# GPIOs.net
KiCad netlist of a schematic drawn in Altium Designer
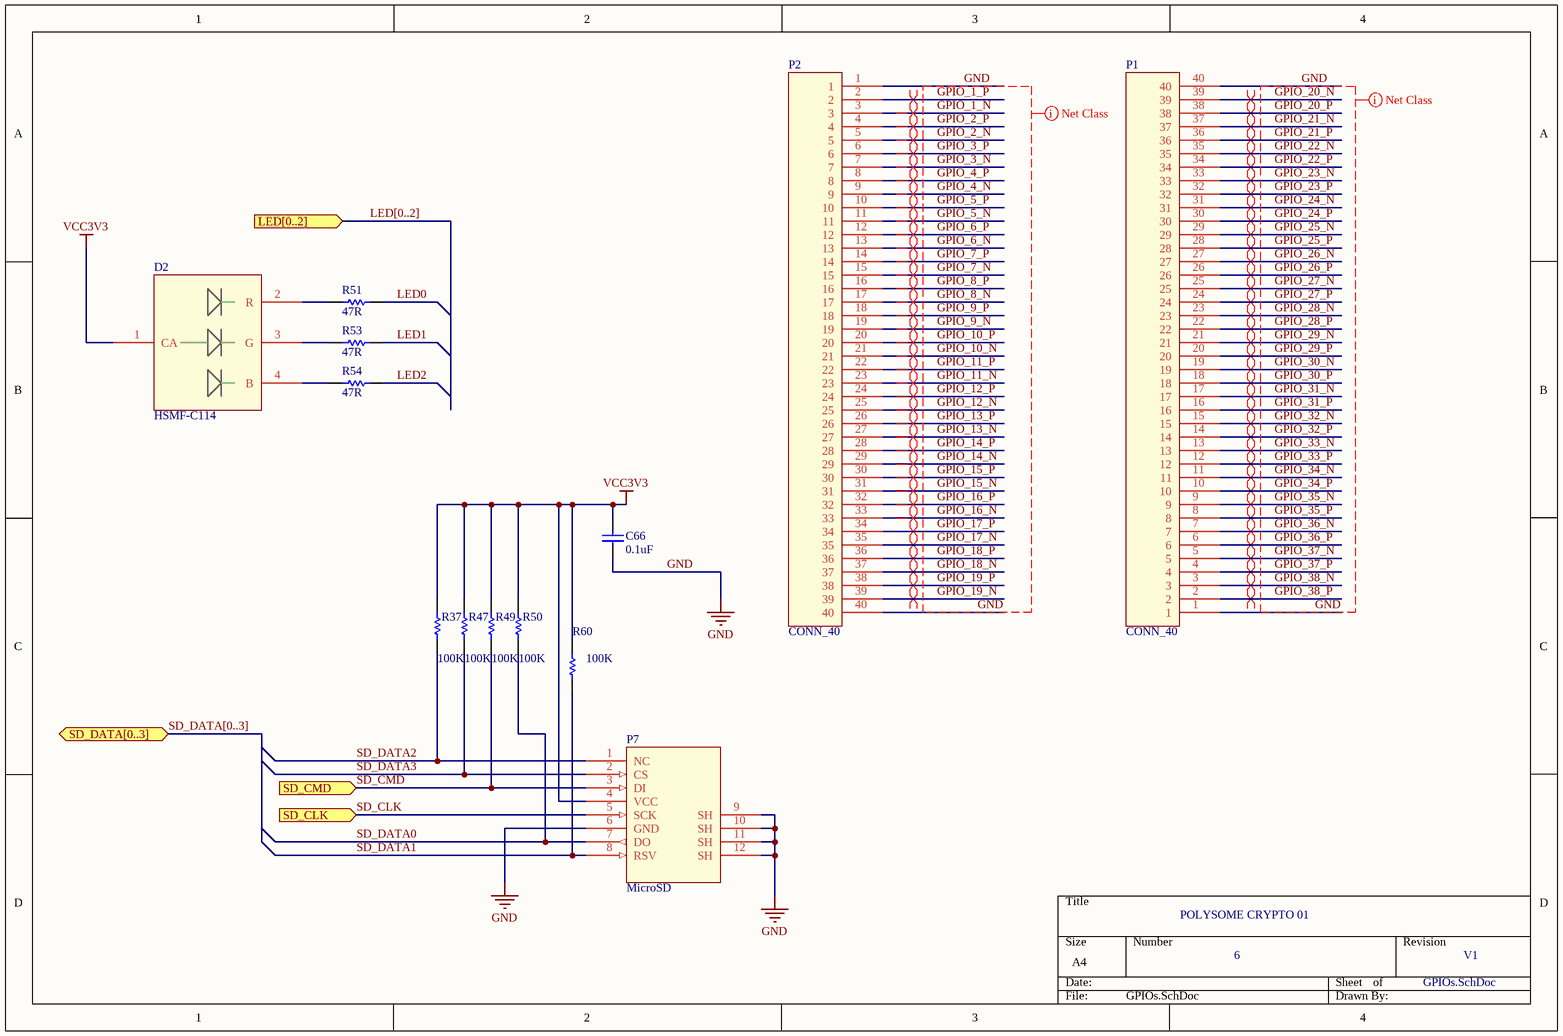
[diagram p0: GPIOs.SchDoc]

(export (version "E")
  (design (tool "Eeschema 10.0.6"))
  (components
    (comp (ref "C66")
      (value "0.1uF")
      (footprint "0402")
      (description "Capacitor (Semiconductor SIM Model)")
      (fields (field (name "Comment") "Cap Semi") (field (name "PUBLISHER") "Altium Limited"))
      (libsource (lib "Miscellaneous Devices") (part "Cap Semi"))
    )
    (comp (ref "D2")
      (value "HSMF-C114")
      (footprint "DFN110P150X35-4N")
      (description "LED CHIP RGB 1.6X1.5X0.35MM SMD")
      (fields (field (name "MANUFACTURER") "Avago Technologies US Inc."))
      (libsource (lib "PolySomeCrypto01") (part "HSMF-C114"))
    )
    (comp (ref "P1")
      (value "CONN_40")
      (footprint "FH12-40S-0.5SH")
      (libsource (lib "PolySomeCrypto01") (part "CONN_40"))
    )
    (comp (ref "P2") (value "CONN_40") (footprint "FH12-40S-0.5SH") (libsource (lib "") (part "CONN_40_1")))
    (comp (ref "P7")
      (value "MicroSD")
      (footprint "MicroSD")
      (libsource (lib "PolySomeCrypto01") (part "MicroSD"))
    )
    (comp (ref "R37")
      (value "100K")
      (description "Semiconductor Resistor")
      (fields (field (name "Comment") "Res Semi") (field (name "PUBLISHER") "Altium Limited"))
      (libsource (lib "Miscellaneous Devices") (part "Res Semi"))
    )
    (comp (ref "R47")
      (value "100K")
      (description "Semiconductor Resistor")
      (fields (field (name "Comment") "Res Semi") (field (name "PUBLISHER") "Altium Limited"))
      (libsource (lib "Miscellaneous Devices") (part "Res Semi"))
    )
    (comp (ref "R49")
      (value "100K")
      (description "Semiconductor Resistor")
      (fields (field (name "Comment") "Res Semi") (field (name "PUBLISHER") "Altium Limited"))
      (libsource (lib "Miscellaneous Devices") (part "Res Semi"))
    )
    (comp (ref "R50")
      (value "100K")
      (description "Semiconductor Resistor")
      (fields (field (name "Comment") "Res Semi") (field (name "PUBLISHER") "Altium Limited"))
      (libsource (lib "Miscellaneous Devices") (part "Res Semi"))
    )
    (comp (ref "R51")
      (value "47R")
      (description "Semiconductor Resistor")
      (fields (field (name "Comment") "Res Semi") (field (name "PUBLISHER") "Altium Limited"))
      (libsource (lib "Miscellaneous Devices") (part "Res Semi"))
    )
    (comp (ref "R53")
      (value "47R")
      (description "Semiconductor Resistor")
      (fields (field (name "Comment") "Res Semi") (field (name "PUBLISHER") "Altium Limited"))
      (libsource (lib "Miscellaneous Devices") (part "Res Semi"))
    )
    (comp (ref "R54")
      (value "47R")
      (description "Semiconductor Resistor")
      (fields (field (name "Comment") "Res Semi") (field (name "PUBLISHER") "Altium Limited"))
      (libsource (lib "Miscellaneous Devices") (part "Res Semi"))
    )
    (comp (ref "R60")
      (value "100K")
      (footprint "0402")
      (description "Semiconductor Resistor")
      (fields (field (name "Comment") "Res Semi") (field (name "PUBLISHER") "Altium Limited"))
      (libsource (lib "Miscellaneous Devices") (part "Res Semi"))
    )
  )
  (nets
    (net (code "1") (name "/GPIO_1_N") (class "Default")
      (node (ref "P2") (pin "3") (pinfunction "3_3") (pintype "passive"))
    )
    (net (code "2") (name "/GPIO_1_P") (class "Default")
      (node (ref "P2") (pin "2") (pinfunction "2_2") (pintype "passive"))
    )
    (net (code "3") (name "/GPIO_2_N") (class "Default")
      (node (ref "P2") (pin "5") (pinfunction "5_5") (pintype "passive"))
    )
    (net (code "4") (name "/GPIO_2_P") (class "Default")
      (node (ref "P2") (pin "4") (pinfunction "4_4") (pintype "passive"))
    )
    (net (code "5") (name "/GPIO_3_N") (class "Default")
      (node (ref "P2") (pin "7") (pinfunction "7_7") (pintype "passive"))
    )
    (net (code "6") (name "/GPIO_3_P") (class "Default")
      (node (ref "P2") (pin "6") (pinfunction "6_6") (pintype "passive"))
    )
    (net (code "7") (name "/GPIO_4_N") (class "Default")
      (node (ref "P2") (pin "9") (pinfunction "9_9") (pintype "passive"))
    )
    (net (code "8") (name "/GPIO_4_P") (class "Default")
      (node (ref "P2") (pin "8") (pinfunction "8_8") (pintype "passive"))
    )
    (net (code "9") (name "/GPIO_5_N") (class "Default")
      (node (ref "P2") (pin "11") (pinfunction "11_11") (pintype "passive"))
    )
    (net (code "10") (name "/GPIO_5_P") (class "Default")
      (node (ref "P2") (pin "10") (pinfunction "10_10") (pintype "passive"))
    )
    (net (code "11") (name "/GPIO_6_N") (class "Default")
      (node (ref "P2") (pin "13") (pinfunction "13_13") (pintype "passive"))
    )
    (net (code "12") (name "/GPIO_6_P") (class "Default")
      (node (ref "P2") (pin "12") (pinfunction "12_12") (pintype "passive"))
    )
    (net (code "13") (name "/GPIO_7_N") (class "Default")
      (node (ref "P2") (pin "15") (pinfunction "15_15") (pintype "passive"))
    )
    (net (code "14") (name "/GPIO_7_P") (class "Default")
      (node (ref "P2") (pin "14") (pinfunction "14_14") (pintype "passive"))
    )
    (net (code "15") (name "/GPIO_8_N") (class "Default")
      (node (ref "P2") (pin "17") (pinfunction "17_17") (pintype "passive"))
    )
    (net (code "16") (name "/GPIO_8_P") (class "Default")
      (node (ref "P2") (pin "16") (pinfunction "16_16") (pintype "passive"))
    )
    (net (code "17") (name "/GPIO_9_N") (class "Default")
      (node (ref "P2") (pin "19") (pinfunction "19_19") (pintype "passive"))
    )
    (net (code "18") (name "/GPIO_9_P") (class "Default")
      (node (ref "P2") (pin "18") (pinfunction "18_18") (pintype "passive"))
    )
    (net (code "19") (name "/GPIO_10_N") (class "Default")
      (node (ref "P2") (pin "21") (pinfunction "21_21") (pintype "passive"))
    )
    (net (code "20") (name "/GPIO_10_P") (class "Default")
      (node (ref "P2") (pin "20") (pinfunction "20_20") (pintype "passive"))
    )
    (net (code "21") (name "/GPIO_11_N") (class "Default")
      (node (ref "P2") (pin "23") (pinfunction "23_23") (pintype "passive"))
    )
    (net (code "22") (name "/GPIO_11_P") (class "Default")
      (node (ref "P2") (pin "22") (pinfunction "22_22") (pintype "passive"))
    )
    (net (code "23") (name "/GPIO_12_N") (class "Default")
      (node (ref "P2") (pin "25") (pinfunction "25_25") (pintype "passive"))
    )
    (net (code "24") (name "/GPIO_12_P") (class "Default")
      (node (ref "P2") (pin "24") (pinfunction "24_24") (pintype "passive"))
    )
    (net (code "25") (name "/GPIO_13_N") (class "Default")
      (node (ref "P2") (pin "27") (pinfunction "27_27") (pintype "passive"))
    )
    (net (code "26") (name "/GPIO_13_P") (class "Default")
      (node (ref "P2") (pin "26") (pinfunction "26_26") (pintype "passive"))
    )
    (net (code "27") (name "/GPIO_14_N") (class "Default")
      (node (ref "P2") (pin "29") (pinfunction "29_29") (pintype "passive"))
    )
    (net (code "28") (name "/GPIO_14_P") (class "Default")
      (node (ref "P2") (pin "28") (pinfunction "28_28") (pintype "passive"))
    )
    (net (code "29") (name "/GPIO_15_N") (class "Default")
      (node (ref "P2") (pin "31") (pinfunction "31_31") (pintype "passive"))
    )
    (net (code "30") (name "/GPIO_15_P") (class "Default")
      (node (ref "P2") (pin "30") (pinfunction "30_30") (pintype "passive"))
    )
    (net (code "31") (name "/GPIO_16_N") (class "Default")
      (node (ref "P2") (pin "33") (pinfunction "33_33") (pintype "passive"))
    )
    (net (code "32") (name "/GPIO_16_P") (class "Default")
      (node (ref "P2") (pin "32") (pinfunction "32_32") (pintype "passive"))
    )
    (net (code "33") (name "/GPIO_17_N") (class "Default")
      (node (ref "P2") (pin "35") (pinfunction "35_35") (pintype "passive"))
    )
    (net (code "34") (name "/GPIO_17_P") (class "Default")
      (node (ref "P2") (pin "34") (pinfunction "34_34") (pintype "passive"))
    )
    (net (code "35") (name "/GPIO_18_N") (class "Default")
      (node (ref "P2") (pin "37") (pinfunction "37_37") (pintype "passive"))
    )
    (net (code "36") (name "/GPIO_18_P") (class "Default")
      (node (ref "P2") (pin "36") (pinfunction "36_36") (pintype "passive"))
    )
    (net (code "37") (name "/GPIO_19_N") (class "Default")
      (node (ref "P2") (pin "39") (pinfunction "39_39") (pintype "passive"))
    )
    (net (code "38") (name "/GPIO_19_P") (class "Default")
      (node (ref "P2") (pin "38") (pinfunction "38_38") (pintype "passive"))
    )
    (net (code "39") (name "/GPIO_20_N") (class "Default")
      (node (ref "P1") (pin "39") (pinfunction "39_39") (pintype "passive"))
    )
    (net (code "40") (name "/GPIO_20_P") (class "Default")
      (node (ref "P1") (pin "38") (pinfunction "38_38") (pintype "passive"))
    )
    (net (code "41") (name "/GPIO_21_N") (class "Default")
      (node (ref "P1") (pin "37") (pinfunction "37_37") (pintype "passive"))
    )
    (net (code "42") (name "/GPIO_21_P") (class "Default")
      (node (ref "P1") (pin "36") (pinfunction "36_36") (pintype "passive"))
    )
    (net (code "43") (name "/GPIO_22_N") (class "Default")
      (node (ref "P1") (pin "35") (pinfunction "35_35") (pintype "passive"))
    )
    (net (code "44") (name "/GPIO_22_P") (class "Default")
      (node (ref "P1") (pin "34") (pinfunction "34_34") (pintype "passive"))
    )
    (net (code "45") (name "/GPIO_23_N") (class "Default")
      (node (ref "P1") (pin "33") (pinfunction "33_33") (pintype "passive"))
    )
    (net (code "46") (name "/GPIO_23_P") (class "Default")
      (node (ref "P1") (pin "32") (pinfunction "32_32") (pintype "passive"))
    )
    (net (code "47") (name "/GPIO_24_N") (class "Default")
      (node (ref "P1") (pin "31") (pinfunction "31_31") (pintype "passive"))
    )
    (net (code "48") (name "/GPIO_24_P") (class "Default")
      (node (ref "P1") (pin "30") (pinfunction "30_30") (pintype "passive"))
    )
    (net (code "49") (name "/GPIO_25_N") (class "Default")
      (node (ref "P1") (pin "29") (pinfunction "29_29") (pintype "passive"))
    )
    (net (code "50") (name "/GPIO_25_P") (class "Default")
      (node (ref "P1") (pin "28") (pinfunction "28_28") (pintype "passive"))
    )
    (net (code "51") (name "/GPIO_26_N") (class "Default")
      (node (ref "P1") (pin "27") (pinfunction "27_27") (pintype "passive"))
    )
    (net (code "52") (name "/GPIO_26_P") (class "Default")
      (node (ref "P1") (pin "26") (pinfunction "26_26") (pintype "passive"))
    )
    (net (code "53") (name "/GPIO_27_N") (class "Default")
      (node (ref "P1") (pin "25") (pinfunction "25_25") (pintype "passive"))
    )
    (net (code "54") (name "/GPIO_27_P") (class "Default")
      (node (ref "P1") (pin "24") (pinfunction "24_24") (pintype "passive"))
    )
    (net (code "55") (name "/GPIO_28_N") (class "Default")
      (node (ref "P1") (pin "23") (pinfunction "23_23") (pintype "passive"))
    )
    (net (code "56") (name "/GPIO_28_P") (class "Default")
      (node (ref "P1") (pin "22") (pinfunction "22_22") (pintype "passive"))
    )
    (net (code "57") (name "/GPIO_29_N") (class "Default")
      (node (ref "P1") (pin "21") (pinfunction "21_21") (pintype "passive"))
    )
    (net (code "58") (name "/GPIO_29_P") (class "Default")
      (node (ref "P1") (pin "20") (pinfunction "20_20") (pintype "passive"))
    )
    (net (code "59") (name "/GPIO_30_N") (class "Default")
      (node (ref "P1") (pin "19") (pinfunction "19_19") (pintype "passive"))
    )
    (net (code "60") (name "/GPIO_30_P") (class "Default")
      (node (ref "P1") (pin "18") (pinfunction "18_18") (pintype "passive"))
    )
    (net (code "61") (name "/GPIO_31_N") (class "Default")
      (node (ref "P1") (pin "17") (pinfunction "17_17") (pintype "passive"))
    )
    (net (code "62") (name "/GPIO_31_P") (class "Default")
      (node (ref "P1") (pin "16") (pinfunction "16_16") (pintype "passive"))
    )
    (net (code "63") (name "/GPIO_32_N") (class "Default")
      (node (ref "P1") (pin "15") (pinfunction "15_15") (pintype "passive"))
    )
    (net (code "64") (name "/GPIO_32_P") (class "Default")
      (node (ref "P1") (pin "14") (pinfunction "14_14") (pintype "passive"))
    )
    (net (code "65") (name "/GPIO_33_N") (class "Default")
      (node (ref "P1") (pin "13") (pinfunction "13_13") (pintype "passive"))
    )
    (net (code "66") (name "/GPIO_33_P") (class "Default")
      (node (ref "P1") (pin "12") (pinfunction "12_12") (pintype "passive"))
    )
    (net (code "67") (name "/GPIO_34_N") (class "Default")
      (node (ref "P1") (pin "11") (pinfunction "11_11") (pintype "passive"))
    )
    (net (code "68") (name "/GPIO_34_P") (class "Default")
      (node (ref "P1") (pin "10") (pinfunction "10_10") (pintype "passive"))
    )
    (net (code "69") (name "/GPIO_35_N") (class "Default")
      (node (ref "P1") (pin "9") (pinfunction "9_9") (pintype "passive"))
    )
    (net (code "70") (name "/GPIO_35_P") (class "Default")
      (node (ref "P1") (pin "8") (pinfunction "8_8") (pintype "passive"))
    )
    (net (code "71") (name "/GPIO_36_N") (class "Default")
      (node (ref "P1") (pin "7") (pinfunction "7_7") (pintype "passive"))
    )
    (net (code "72") (name "/GPIO_36_P") (class "Default")
      (node (ref "P1") (pin "6") (pinfunction "6_6") (pintype "passive"))
    )
    (net (code "73") (name "/GPIO_37_N") (class "Default")
      (node (ref "P1") (pin "5") (pinfunction "5_5") (pintype "passive"))
    )
    (net (code "74") (name "/GPIO_37_P") (class "Default")
      (node (ref "P1") (pin "4") (pinfunction "4_4") (pintype "passive"))
    )
    (net (code "75") (name "/GPIO_38_N") (class "Default")
      (node (ref "P1") (pin "3") (pinfunction "3_3") (pintype "passive"))
    )
    (net (code "76") (name "/GPIO_38_P") (class "Default")
      (node (ref "P1") (pin "2") (pinfunction "2_2") (pintype "passive"))
    )
    (net (code "77") (name "/LED0") (class "Default")
      (node (ref "R51") (pin "2") (pinfunction "2_2") (pintype "passive"))
    )
    (net (code "78") (name "/LED1") (class "Default")
      (node (ref "R53") (pin "2") (pinfunction "2_2") (pintype "passive"))
    )
    (net (code "79") (name "/LED2") (class "Default")
      (node (ref "R54") (pin "2") (pinfunction "2_2") (pintype "passive"))
    )
    (net (code "81") (name "/SD_CLK") (class "Default")
      (node (ref "P7") (pin "5") (pinfunction "SCK_5") (pintype "input"))
    )
    (net (code "82") (name "/SD_CMD") (class "Default")
      (node (ref "P7") (pin "3") (pinfunction "DI_3") (pintype "input"))
      (node (ref "R49") (pin "1") (pinfunction "1_1") (pintype "passive"))
    )
    (net (code "83") (name "/SD_DATA0") (class "Default")
      (node (ref "P7") (pin "7") (pinfunction "DO_7") (pintype "output"))
      (node (ref "R50") (pin "1") (pinfunction "1_1") (pintype "passive"))
    )
    (net (code "84") (name "/SD_DATA1") (class "Default")
      (node (ref "P7") (pin "8") (pinfunction "RSV_8") (pintype "input"))
      (node (ref "R60") (pin "1") (pinfunction "1_1") (pintype "passive"))
    )
    (net (code "85") (name "/SD_DATA2") (class "Default")
      (node (ref "P7") (pin "1") (pinfunction "NC_1") (pintype "tri_state"))
      (node (ref "R37") (pin "1") (pinfunction "1_1") (pintype "passive"))
    )
    (net (code "86") (name "/SD_DATA3") (class "Default")
      (node (ref "P7") (pin "2") (pinfunction "CS_2") (pintype "input"))
      (node (ref "R47") (pin "1") (pinfunction "1_1") (pintype "passive"))
    )
    (net (code "88") (name "GND") (class "Default")
      (node (ref "C66") (pin "1") (pinfunction "1_1") (pintype "passive"))
      (node (ref "P1") (pin "1") (pinfunction "1_1") (pintype "passive"))
      (node (ref "P1") (pin "40") (pinfunction "40_40") (pintype "passive"))
      (node (ref "P2") (pin "1") (pinfunction "1_1") (pintype "passive"))
      (node (ref "P2") (pin "40") (pinfunction "40_40") (pintype "passive"))
      (node (ref "P7") (pin "10") (pinfunction "SH_10") (pintype "power_in"))
      (node (ref "P7") (pin "11") (pinfunction "SH_11") (pintype "power_in"))
      (node (ref "P7") (pin "12") (pinfunction "SH_12") (pintype "power_in"))
      (node (ref "P7") (pin "6") (pinfunction "GND_6") (pintype "power_in"))
      (node (ref "P7") (pin "9") (pinfunction "SH_9") (pintype "power_in"))
    )
    (net (code "89") (name "Net-(D2-B)") (class "Default")
      (node (ref "D2") (pin "4") (pinfunction "B_4") (pintype "passive"))
      (node (ref "R54") (pin "1") (pinfunction "1_1") (pintype "passive"))
    )
    (net (code "90") (name "Net-(D2-G)") (class "Default")
      (node (ref "D2") (pin "3") (pinfunction "G_3") (pintype "passive"))
      (node (ref "R53") (pin "1") (pinfunction "1_1") (pintype "passive"))
    )
    (net (code "91") (name "Net-(D2-R)") (class "Default")
      (node (ref "D2") (pin "2") (pinfunction "R_2") (pintype "passive"))
      (node (ref "R51") (pin "1") (pinfunction "1_1") (pintype "passive"))
    )
    (net (code "92") (name "VCC3V3") (class "Default")
      (node (ref "C66") (pin "2") (pinfunction "2_2") (pintype "passive"))
      (node (ref "D2") (pin "1") (pinfunction "CA_1") (pintype "passive"))
      (node (ref "P7") (pin "4") (pinfunction "VCC_4") (pintype "power_in"))
      (node (ref "R37") (pin "2") (pinfunction "2_2") (pintype "passive"))
      (node (ref "R47") (pin "2") (pinfunction "2_2") (pintype "passive"))
      (node (ref "R49") (pin "2") (pinfunction "2_2") (pintype "passive"))
      (node (ref "R50") (pin "2") (pinfunction "2_2") (pintype "passive"))
      (node (ref "R60") (pin "2") (pinfunction "2_2") (pintype "passive"))
    )
  )
)
